# Capacitor.net
KiCad netlist of a schematic drawn in Altium Designer
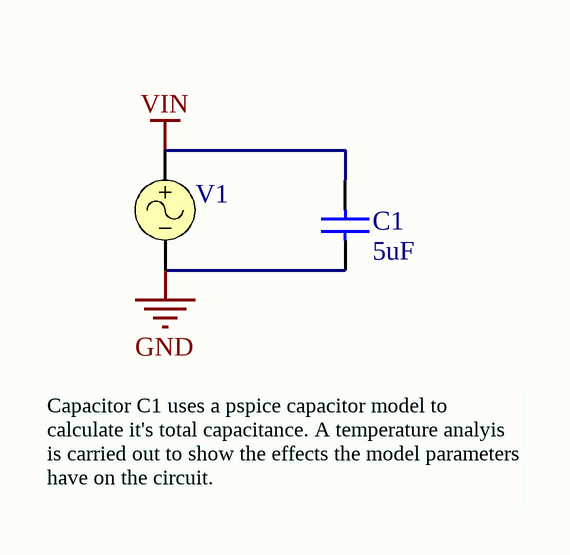
[diagram p0: Capacitor.SchDoc]

(export (version "E")
  (design (tool "Eeschema 10.0.6"))
  (components
    (comp (ref "C1")
      (value "5uF")
      (footprint "RAD-0.3")
      (description "Capacitor")
      (fields (field (name "Comment") "Cap") (field (name "PUBLISHER") "Altium Limited"))
      (libsource (lib "Miscellaneous Devices") (part "Cap"))
    )
    (comp (ref "V1")
      (value "VSIN")
      (description "Sinusoidal Voltage Source")
      (fields (field (name "PUBLISHER") "Altium Limited"))
      (libsource (lib "Simulation Sources") (part "VSIN"))
    )
  )
  (nets
    (net (code "1") (name "GND") (class "Default")
      (node (ref "C1") (pin "2") (pinfunction "2_2") (pintype "passive"))
      (node (ref "V1") (pin "2") (pinfunction "2_2") (pintype "passive"))
    )
    (net (code "2") (name "VIN") (class "Default")
      (node (ref "C1") (pin "1") (pinfunction "1_1") (pintype "passive"))
      (node (ref "V1") (pin "1") (pinfunction "1_1") (pintype "passive"))
    )
  )
)
